# main.net
KiCad netlist of a schematic drawn in Altium Designer
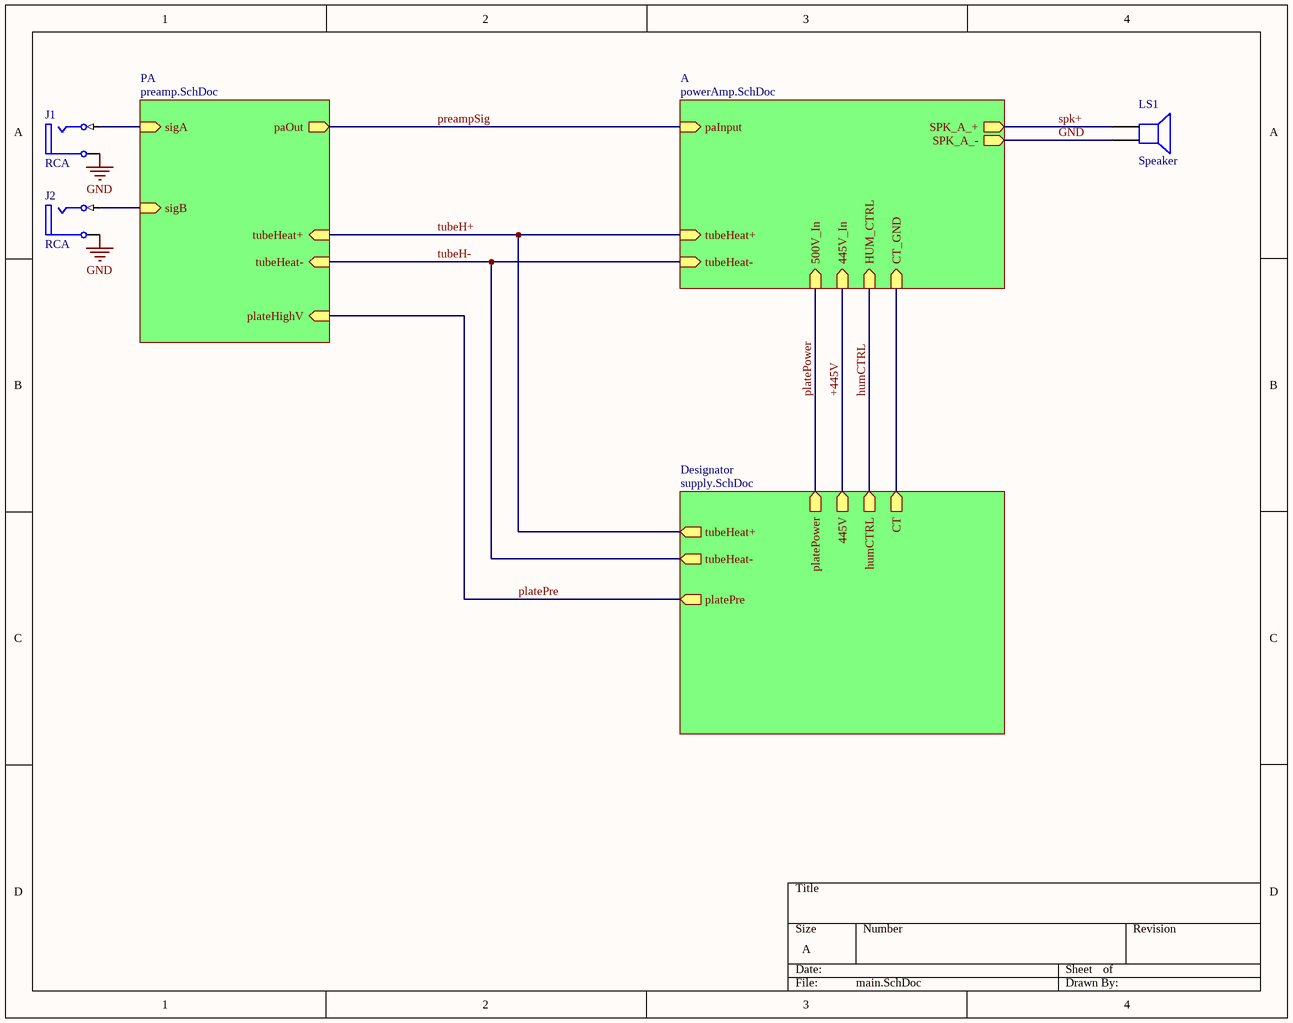
[diagram p0: main.SchDoc]

(export (version "E")
  (design (tool "Eeschema 10.0.6"))
  (components
    (comp (ref "J1")
      (value "RCA")
      (footprint "RCA/4.5-H2")
      (description "RCA Phono Jack, Right Angle, Thru-Hole, Snap-In")
      (fields (field (name "PUBLISHER") "Altium Limited"))
      (libsource (lib "Miscellaneous Connectors") (part "RCA"))
    )
    (comp (ref "J2")
      (value "RCA")
      (footprint "RCA/4.5-H2")
      (description "RCA Phono Jack, Right Angle, Thru-Hole, Snap-In")
      (fields (field (name "PUBLISHER") "Altium Limited"))
      (libsource (lib "Miscellaneous Connectors") (part "RCA"))
    )
    (comp (ref "LS1")
      (value "Speaker")
      (footprint "PIN2")
      (description "Loudspeaker")
      (fields (field (name "PUBLISHER") "Altium Limited"))
      (libsource (lib "Miscellaneous Devices") (part "Speaker"))
    )
  )
  (nets
    (net (code "7") (name "/sigA") (class "Default")
      (node (ref "J1") (pin "2B") (pinfunction "Signal_2B") (pintype "input"))
    )
    (net (code "8") (name "/sigB") (class "Default")
      (node (ref "J2") (pin "2B") (pinfunction "Signal_2B") (pintype "input"))
    )
    (net (code "9") (name "/spk+") (class "Default")
      (node (ref "LS1") (pin "1") (pinfunction "1_1") (pintype "passive"))
    )
    (net (code "12") (name "GND") (class "Default")
      (node (ref "J1") (pin "1A") (pinfunction "Ground_1A") (pintype "power_in"))
      (node (ref "J2") (pin "1A") (pinfunction "Ground_1A") (pintype "power_in"))
      (node (ref "LS1") (pin "2") (pinfunction "2_2") (pintype "passive"))
    )
  )
)
